# PrimaryLogger.net
KiCad netlist of a schematic drawn in EAGLE
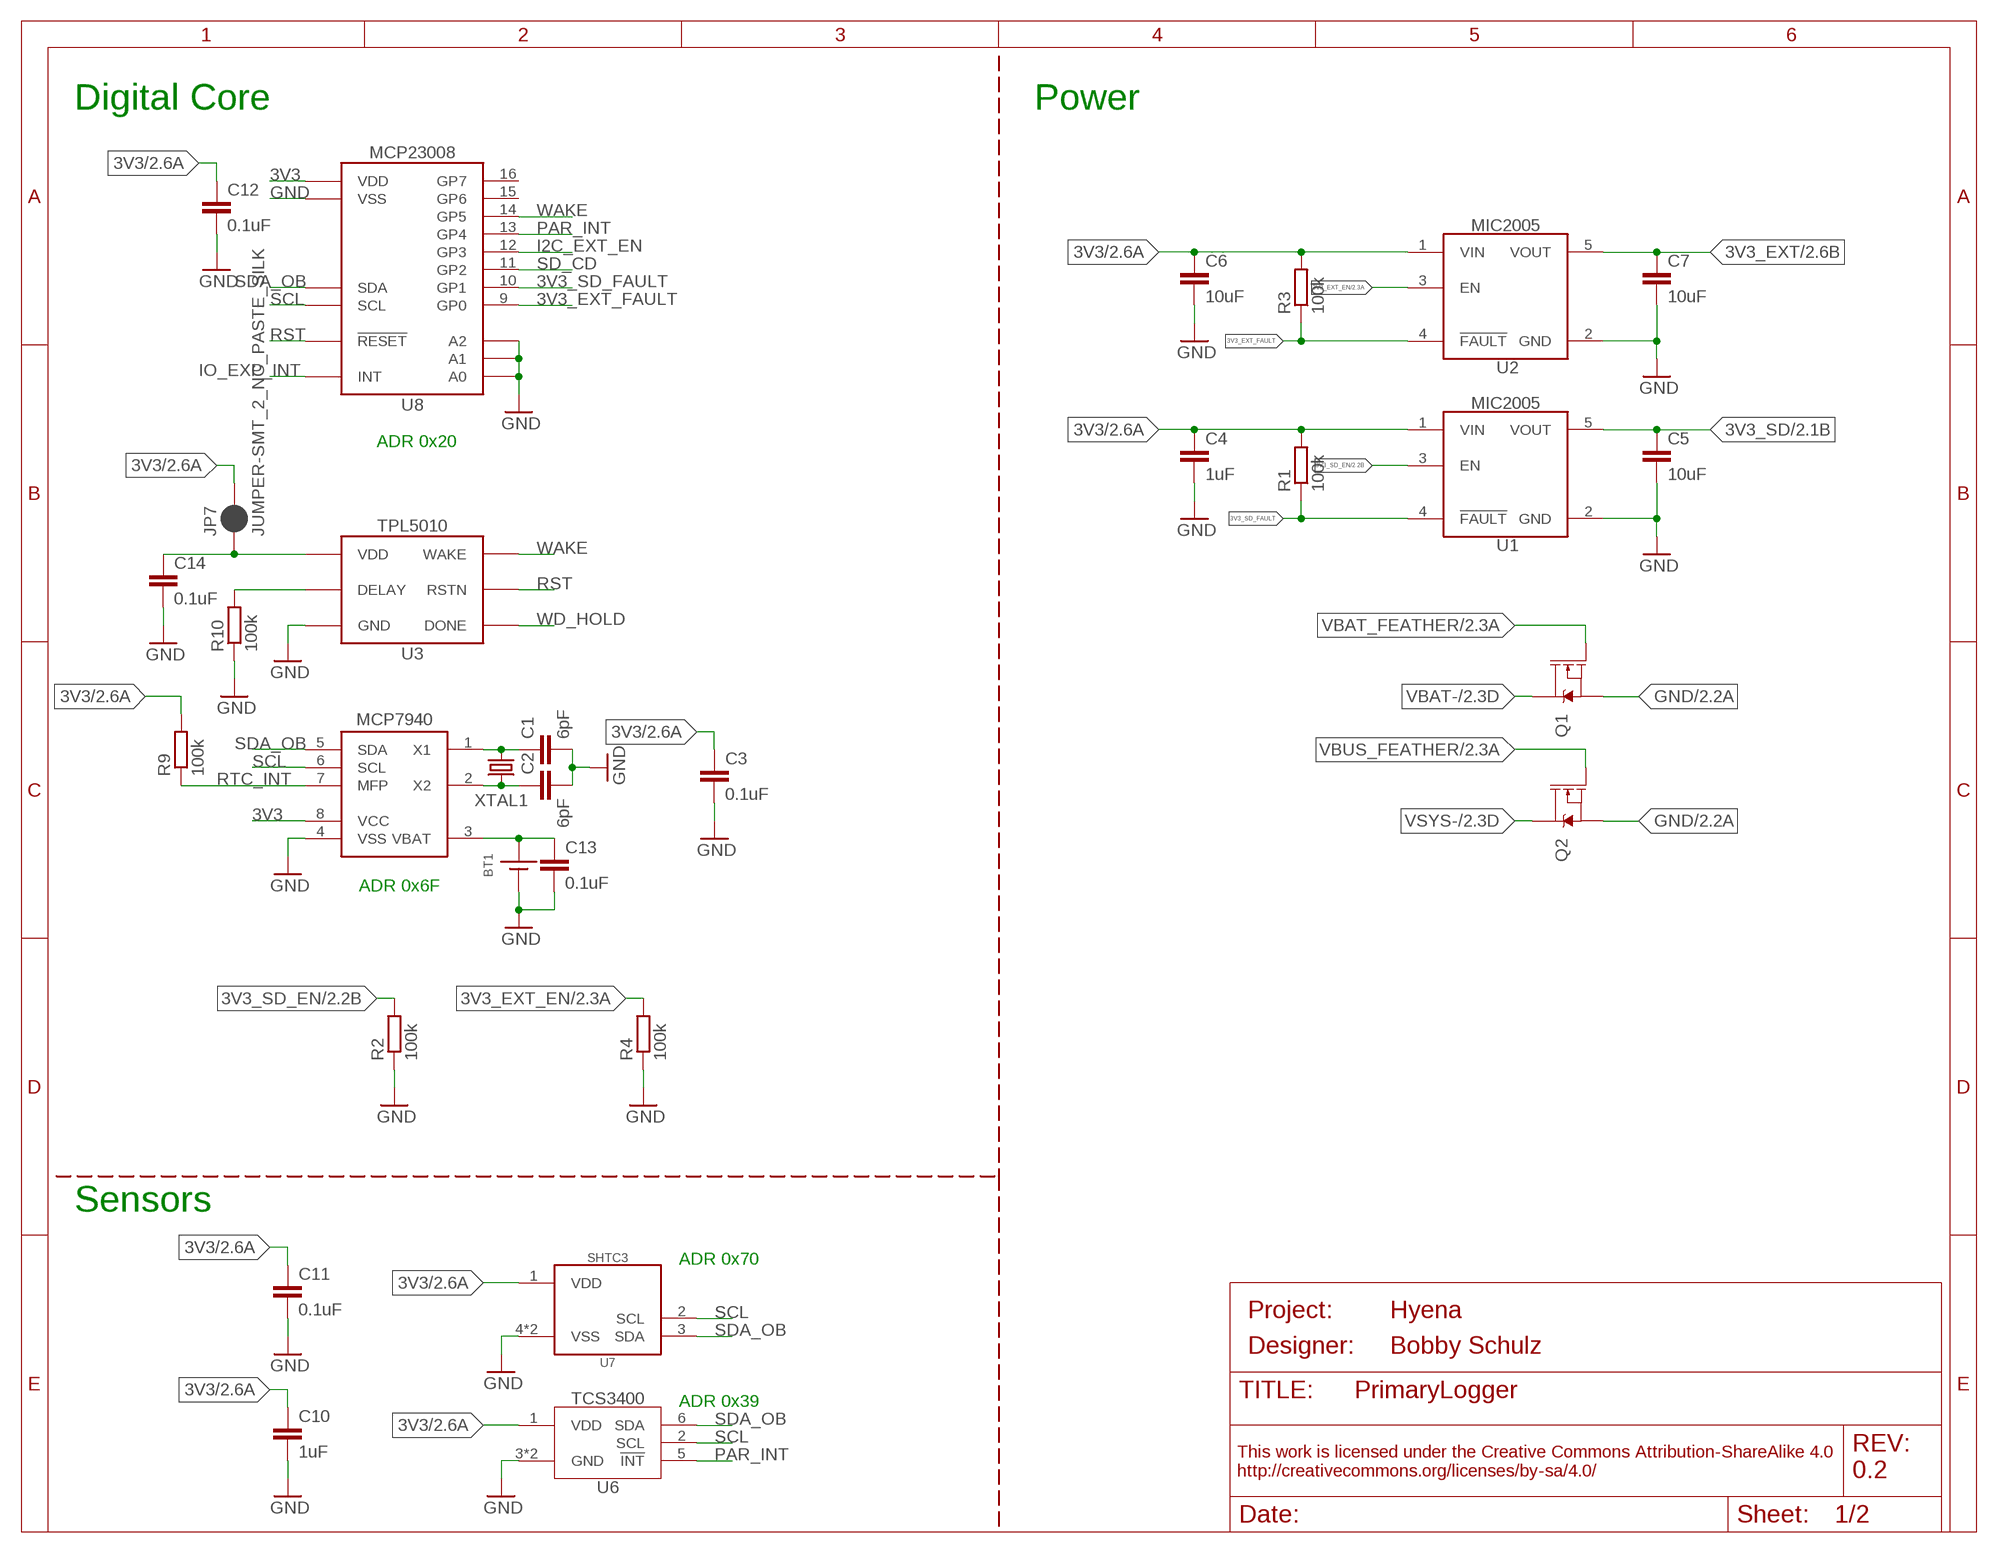
[diagram p0: schematic, sheet 1]
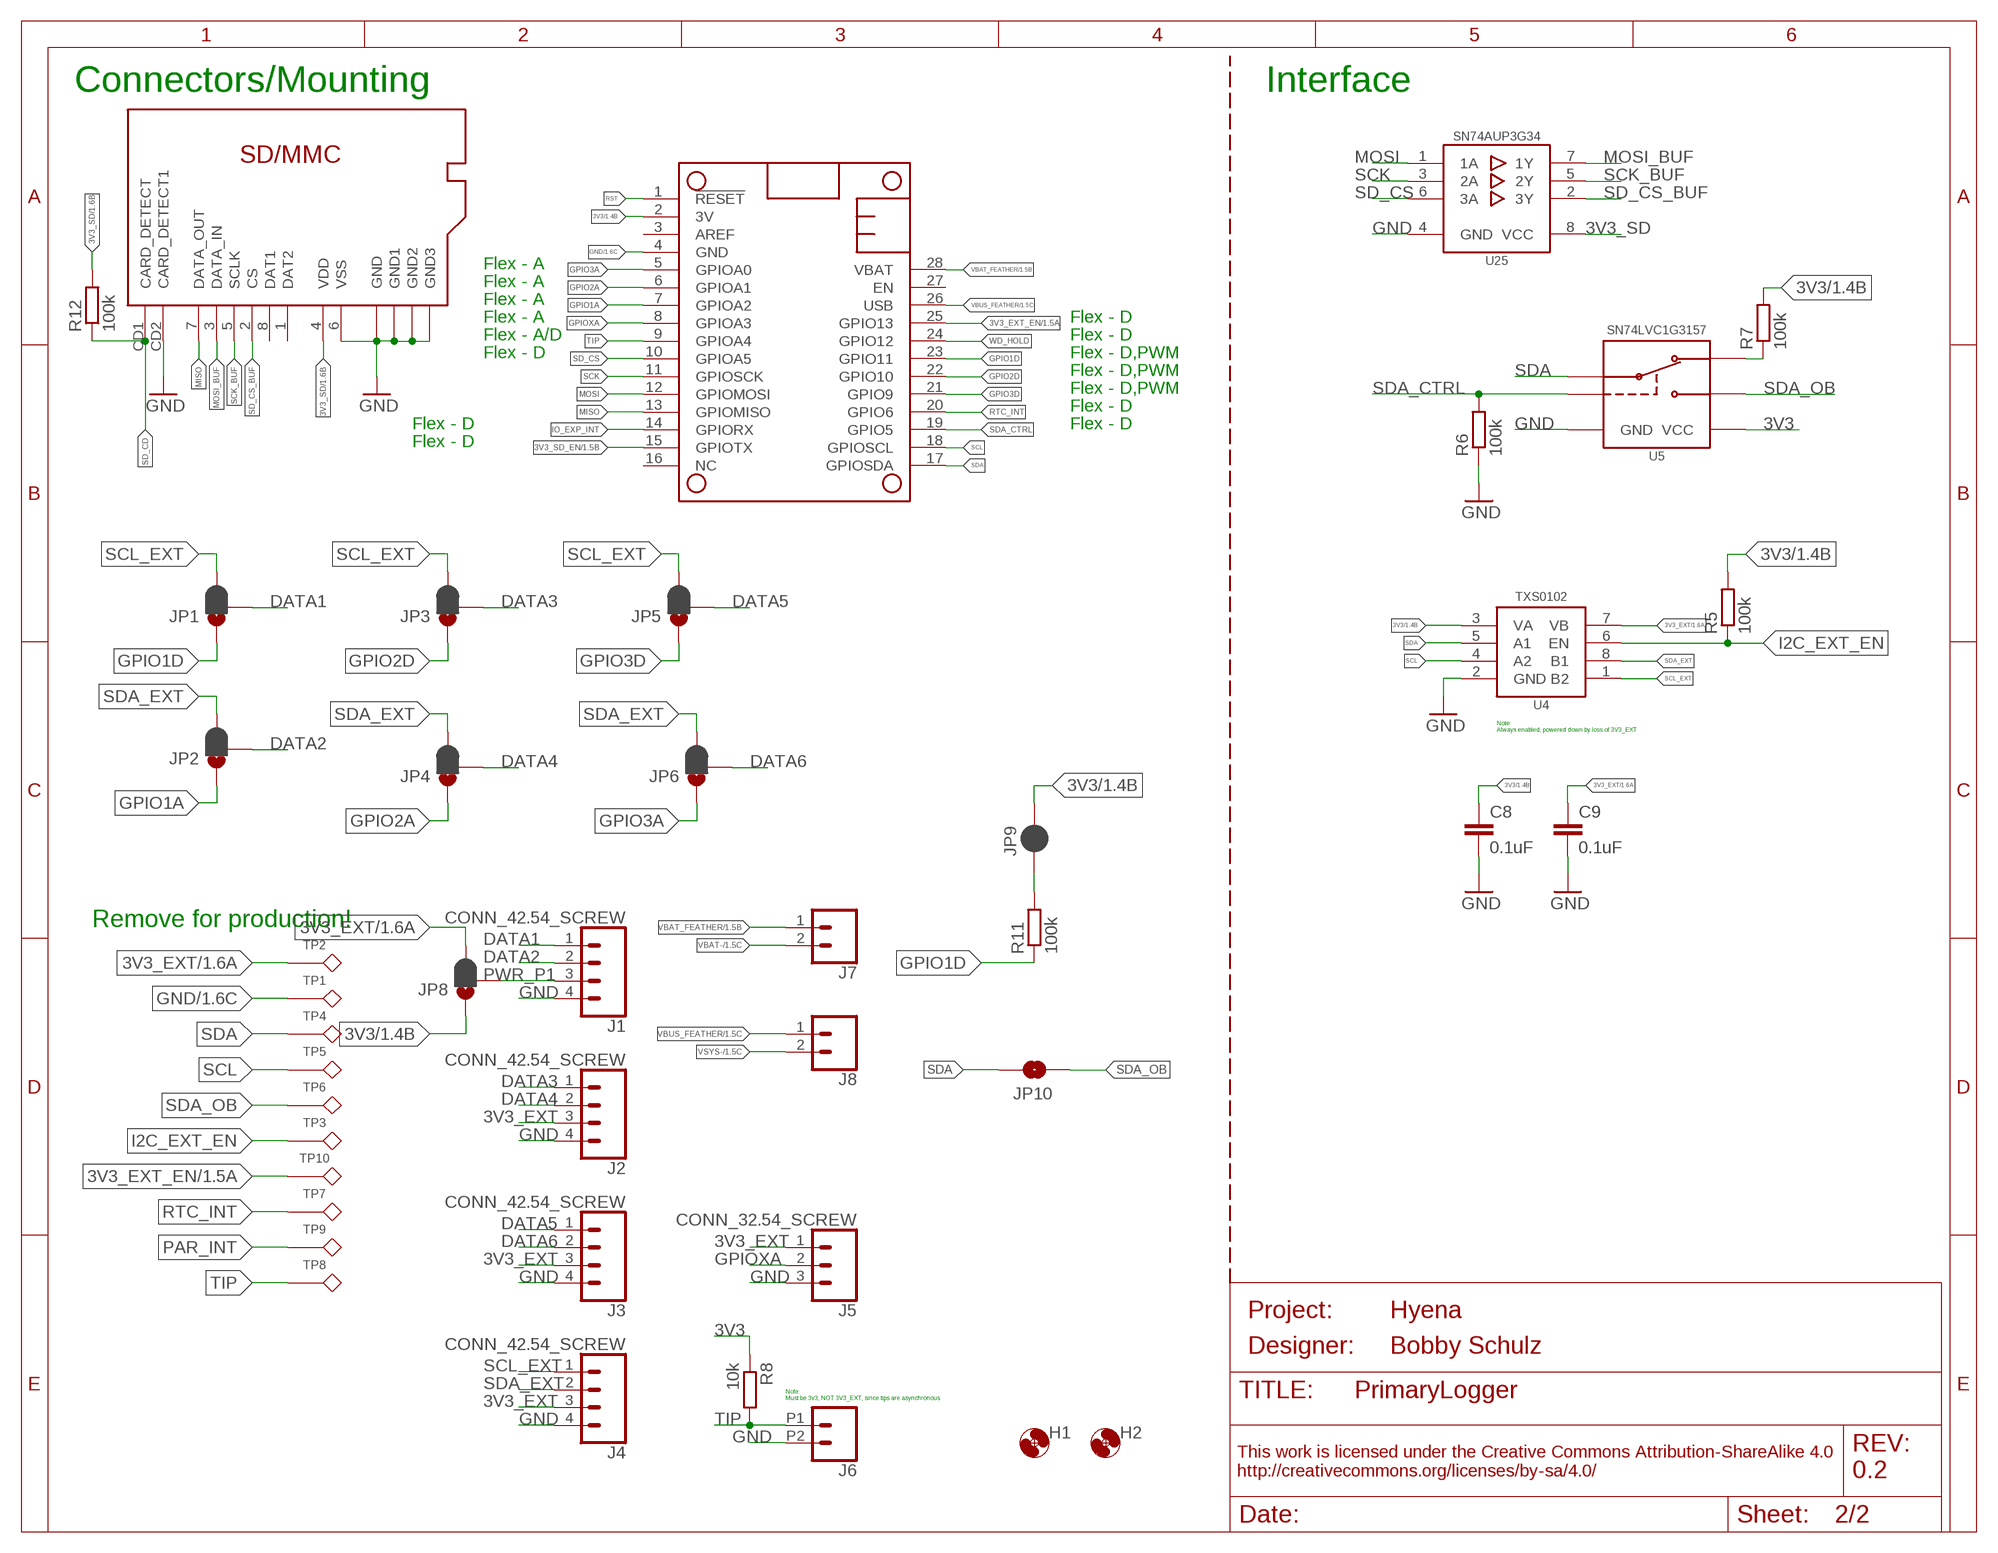
[diagram p1: schematic, sheet 2]

(export (version "E")
  (design (tool "Eeschema 10.0.6"))
  (components
    (comp (ref "BT1")
      (value "BATTERY_COIN12MM")
      (footprint "eagle-import:LINX_BAT-HLD-012-SMT")
      (fields (field (name "MF") "Linx") (field (name "MPN") "BAT-HLD-012-SMT"))
      (libsource (lib "eagle-import") (part "BATTERY_COIN12MM"))
    )
    (comp (ref "C1")
      (value "6pF")
      (footprint "eagle-import:C0402")
      (fields (field (name "MF") "Murata") (field (name "MPN") "GJM1555C1H6R0CB01D"))
      (libsource (lib "eagle-import") (part "C-EUC04026PF"))
    )
    (comp (ref "C2")
      (value "6pF")
      (footprint "eagle-import:C0402")
      (fields (field (name "MF") "Murata") (field (name "MPN") "GJM1555C1H6R0CB01D"))
      (libsource (lib "eagle-import") (part "C-EUC04026PF"))
    )
    (comp (ref "C3")
      (value "0.1uF")
      (footprint "eagle-import:C0603")
      (fields (field (name "MF") "Murata") (field (name "MPN") "GCM188R71E104KA57D"))
      (libsource (lib "eagle-import") (part "C-EUC06030.1UF"))
    )
    (comp (ref "C4")
      (value "1uF")
      (footprint "eagle-import:C0603")
      (fields (field (name "MF") "Yaiyo Yuden") (field (name "MPN") "EMK107BJ105KA-T"))
      (libsource (lib "eagle-import") (part "C-EUC06031UF"))
    )
    (comp (ref "C5")
      (value "10uF")
      (footprint "eagle-import:C0805")
      (fields (field (name "MF") "Murata") (field (name "MPN") "GRM21BR61C106KE15K"))
      (libsource (lib "eagle-import") (part "C-EUC080510UF"))
    )
    (comp (ref "C6")
      (value "10uF")
      (footprint "eagle-import:C0805")
      (fields (field (name "MF") "Murata") (field (name "MPN") "GRM21BR61C106KE15K"))
      (libsource (lib "eagle-import") (part "C-EUC080510UF"))
    )
    (comp (ref "C7")
      (value "10uF")
      (footprint "eagle-import:C0805")
      (fields (field (name "MF") "Murata") (field (name "MPN") "GRM21BR61C106KE15K"))
      (libsource (lib "eagle-import") (part "C-EUC080510UF"))
    )
    (comp (ref "C10")
      (value "1uF")
      (footprint "eagle-import:C0603")
      (fields (field (name "MF") "Yaiyo Yuden") (field (name "MPN") "EMK107BJ105KA-T"))
      (libsource (lib "eagle-import") (part "C-EUC06031UF"))
    )
    (comp (ref "C11")
      (value "0.1uF")
      (footprint "eagle-import:C0603")
      (fields (field (name "MF") "Murata") (field (name "MPN") "GCM188R71E104KA57D"))
      (libsource (lib "eagle-import") (part "C-EUC06030.1UF"))
    )
    (comp (ref "C12")
      (value "0.1uF")
      (footprint "eagle-import:C0603")
      (fields (field (name "MF") "Murata") (field (name "MPN") "GCM188R71E104KA57D"))
      (libsource (lib "eagle-import") (part "C-EUC06030.1UF"))
    )
    (comp (ref "C13")
      (value "0.1uF")
      (footprint "eagle-import:C0603")
      (fields (field (name "MF") "Murata") (field (name "MPN") "GCM188R71E104KA57D"))
      (libsource (lib "eagle-import") (part "C-EUC06030.1UF"))
    )
    (comp (ref "C14")
      (value "0.1uF")
      (footprint "eagle-import:C0603")
      (fields (field (name "MF") "Murata") (field (name "MPN") "GCM188R71E104KA57D"))
      (libsource (lib "eagle-import") (part "C-EUC06030.1UF"))
    )
    (comp (ref "JP7")
      (value "JUMPER-SMT_2_NC_PASTE_SILK")
      (footprint "eagle-import:SMT-JUMPER_2_NC_PASTE_SILK")
      (libsource (lib "eagle-import") (part "JUMPER-SMT_2_NC_PASTE_SILK"))
    )
    (comp (ref "Q1")
      (value "DMG3404")
      (footprint "eagle-import:SOT23-3")
      (fields (field (name "MF") "Diodes Incorporated") (field (name "MPN") "DMG3404L-7"))
      (libsource (lib "eagle-import") (part "MOSFET-NCH-DMG3404L"))
    )
    (comp (ref "Q2")
      (value "DMG3404")
      (footprint "eagle-import:SOT23-3")
      (fields (field (name "MF") "Diodes Incorporated") (field (name "MPN") "DMG3404L-7"))
      (libsource (lib "eagle-import") (part "MOSFET-NCH-DMG3404L"))
    )
    (comp (ref "R1")
      (value "100k")
      (footprint "eagle-import:R0603")
      (fields (field (name "MF") "Yageo") (field (name "MPN") "RC0603FR-07100KL"))
      (libsource (lib "eagle-import") (part "R-EU_R0603100K"))
    )
    (comp (ref "R2")
      (value "100k")
      (footprint "eagle-import:R0603")
      (fields (field (name "MF") "Yageo") (field (name "MPN") "RC0603FR-07100KL"))
      (libsource (lib "eagle-import") (part "R-EU_R0603100K"))
    )
    (comp (ref "R3")
      (value "100k")
      (footprint "eagle-import:R0603")
      (fields (field (name "MF") "Yageo") (field (name "MPN") "RC0603FR-07100KL"))
      (libsource (lib "eagle-import") (part "R-EU_R0603100K"))
    )
    (comp (ref "R4")
      (value "100k")
      (footprint "eagle-import:R0603")
      (fields (field (name "MF") "Yageo") (field (name "MPN") "RC0603FR-07100KL"))
      (libsource (lib "eagle-import") (part "R-EU_R0603100K"))
    )
    (comp (ref "R9")
      (value "100k")
      (footprint "eagle-import:R0603")
      (fields (field (name "MF") "Yageo") (field (name "MPN") "RC0603FR-07100KL"))
      (libsource (lib "eagle-import") (part "R-EU_R0603100K"))
    )
    (comp (ref "R10")
      (value "100k")
      (footprint "eagle-import:R0603")
      (fields (field (name "MF") "Yageo") (field (name "MPN") "RC0603FR-07100KL"))
      (libsource (lib "eagle-import") (part "R-EU_R0603100K"))
    )
    (comp (ref "U1")
      (value "MIC2005")
      (footprint "eagle-import:SOT23-5")
      (fields
        (field (name "DISP") "MIC2005")
        (field (name "MF") "Microchip")
        (field (name "MPN") "MIC2005A-1YM5-TR")
      )
      (libsource (lib "eagle-import") (part "MIC2005"))
    )
    (comp (ref "U2")
      (value "MIC2005")
      (footprint "eagle-import:SOT23-5")
      (fields
        (field (name "DISP") "MIC2005")
        (field (name "MF") "Microchip")
        (field (name "MPN") "MIC2005A-1YM5-TR")
      )
      (libsource (lib "eagle-import") (part "MIC2005"))
    )
    (comp (ref "U3")
      (value "TPL5010DDC")
      (footprint "eagle-import:DDC_R-PDSO-G6")
      (fields (field (name "MF") "TI") (field (name "MPN") "TPL5010DDCT"))
      (libsource (lib "eagle-import") (part "TPL5010DDC"))
    )
    (comp (ref "U6")
      (value "TCS3400")
      (footprint "eagle-import:TCS3400")
      (fields (field (name "MF") "AMS") (field (name "MPN") "TCS34003FNM"))
      (libsource (lib "eagle-import") (part "TCS3400"))
    )
    (comp (ref "U7")
      (value "SHTC3DFN")
      (footprint "eagle-import:DFN_4_2X2")
      (fields (field (name "DISP") "SHTC3") (field (name "MF") "Sensirion") (field (name "MPN") "SHTC3"))
      (libsource (lib "eagle-import") (part "SHTCDFN3"))
    )
    (comp (ref "U8")
      (value "MCP23008QFN")
      (footprint "eagle-import:QFN20")
      (fields (field (name "MF") "Microchip") (field (name "MPN") "MCP23008T-E/ML"))
      (libsource (lib "eagle-import") (part "MCP23008QFN"))
    )
    (comp (ref "U9")
      (value "MCP7940SOIC")
      (footprint "eagle-import:SO08")
      (fields (field (name "MF") "Microchip") (field (name "MPN") "MCP7940N-I/SN"))
      (libsource (lib "eagle-import") (part "MCP7940SOIC"))
    )
    (comp (ref "XTAL1")
      (value "CRYSTAL3.2X1.5")
      (footprint "eagle-import:CRYSTAL_3.2X1.5_2-SMD")
      (fields
        (field (name "DIGIKEY") "535-11937-1-ND")
        (field (name "MF") "ABS07-120-32.768KHZ-T")
        (field (name "MPN") "Abracon")
      )
      (libsource (lib "eagle-import") (part "CRYSTAL3.2X1.5"))
    )
    (comp (ref "C8")
      (value "0.1uF")
      (footprint "eagle-import:C0603")
      (fields (field (name "MF") "Murata") (field (name "MPN") "GCM188R71E104KA57D"))
      (libsource (lib "eagle-import") (part "C-EUC06030.1UF"))
    )
    (comp (ref "C9")
      (value "0.1uF")
      (footprint "eagle-import:C0603")
      (fields (field (name "MF") "Murata") (field (name "MPN") "GCM188R71E104KA57D"))
      (libsource (lib "eagle-import") (part "C-EUC06030.1UF"))
    )
    (comp (ref "H1")
      (value "MOUNTING_HOLE4_NP")
      (footprint "eagle-import:4_40")
      (fields (field (name "MPN") "DNP"))
      (libsource (lib "eagle-import") (part "MOUNTING_HOLE4_NP"))
    )
    (comp (ref "H2")
      (value "MOUNTING_HOLE4_NP")
      (footprint "eagle-import:4_40")
      (fields (field (name "MPN") "DNP"))
      (libsource (lib "eagle-import") (part "MOUNTING_HOLE4_NP"))
    )
    (comp (ref "J1")
      (value "CONN_42.54_SCREW")
      (footprint "eagle-import:1X04_SCREW")
      (fields (field (name "MF") "On Shore") (field (name "MPN") "OSTVN04A150"))
      (libsource (lib "eagle-import") (part "CONN_42.54_SCREW"))
    )
    (comp (ref "J2")
      (value "CONN_42.54_SCREW")
      (footprint "eagle-import:1X04_SCREW")
      (fields (field (name "MF") "On Shore") (field (name "MPN") "OSTVN04A150"))
      (libsource (lib "eagle-import") (part "CONN_42.54_SCREW"))
    )
    (comp (ref "J3")
      (value "CONN_42.54_SCREW")
      (footprint "eagle-import:1X04_SCREW")
      (fields (field (name "MF") "On Shore") (field (name "MPN") "OSTVN04A150"))
      (libsource (lib "eagle-import") (part "CONN_42.54_SCREW"))
    )
    (comp (ref "J4")
      (value "CONN_42.54_SCREW")
      (footprint "eagle-import:1X04_SCREW")
      (fields (field (name "MF") "On Shore") (field (name "MPN") "OSTVN04A150"))
      (libsource (lib "eagle-import") (part "CONN_42.54_SCREW"))
    )
    (comp (ref "J5")
      (value "CONN_32.54_SCREW")
      (footprint "eagle-import:1X03_SCREW")
      (fields (field (name "MF") "On Shore") (field (name "MPN") "OSTVN03A150"))
      (libsource (lib "eagle-import") (part "CONN_32.54_SCREW"))
    )
    (comp (ref "J6")
      (value "CONN_022.54_SCREW_ROUND")
      (footprint "eagle-import:1X02_2.54_SCREWTERM_ROUND")
      (fields (field (name "MF") "OnShore") (field (name "MPN") "OSTVN02A150"))
      (libsource (lib "eagle-import") (part "CONN_022.54_SCREW_ROUND"))
    )
    (comp (ref "J7")
      (value "CONN_023.5MM_ROUND")
      (footprint "eagle-import:SCREWTERMINAL-3.5MM-2_ROUND")
      (fields (field (name "MF") "OnShore") (field (name "MPN") "OSTTE020161"))
      (libsource (lib "eagle-import") (part "CONN_023.5MM_ROUND"))
    )
    (comp (ref "J8")
      (value "CONN_023.5MM_ROUND")
      (footprint "eagle-import:SCREWTERMINAL-3.5MM-2_ROUND")
      (fields (field (name "MF") "OnShore") (field (name "MPN") "OSTTE020161"))
      (libsource (lib "eagle-import") (part "CONN_023.5MM_ROUND"))
    )
    (comp (ref "JP1")
      (value "JUMPER-SMT_3_1-NC_PASTE_SILK")
      (footprint "eagle-import:SMT-JUMPER_3_1-NC_PASTE_SILK")
      (libsource (lib "eagle-import") (part "JUMPER-SMT_3_1-NC_PASTE_SILK"))
    )
    (comp (ref "JP2")
      (value "JUMPER-SMT_3_1-NC_PASTE_SILK")
      (footprint "eagle-import:SMT-JUMPER_3_1-NC_PASTE_SILK")
      (libsource (lib "eagle-import") (part "JUMPER-SMT_3_1-NC_PASTE_SILK"))
    )
    (comp (ref "JP3")
      (value "JUMPER-SMT_3_1-NC_PASTE_SILK")
      (footprint "eagle-import:SMT-JUMPER_3_1-NC_PASTE_SILK")
      (libsource (lib "eagle-import") (part "JUMPER-SMT_3_1-NC_PASTE_SILK"))
    )
    (comp (ref "JP4")
      (value "JUMPER-SMT_3_1-NC_PASTE_SILK")
      (footprint "eagle-import:SMT-JUMPER_3_1-NC_PASTE_SILK")
      (libsource (lib "eagle-import") (part "JUMPER-SMT_3_1-NC_PASTE_SILK"))
    )
    (comp (ref "JP5")
      (value "JUMPER-SMT_3_1-NC_PASTE_SILK")
      (footprint "eagle-import:SMT-JUMPER_3_1-NC_PASTE_SILK")
      (libsource (lib "eagle-import") (part "JUMPER-SMT_3_1-NC_PASTE_SILK"))
    )
    (comp (ref "JP6")
      (value "JUMPER-SMT_3_1-NC_PASTE_SILK")
      (footprint "eagle-import:SMT-JUMPER_3_1-NC_PASTE_SILK")
      (libsource (lib "eagle-import") (part "JUMPER-SMT_3_1-NC_PASTE_SILK"))
    )
    (comp (ref "JP8")
      (value "JUMPER-SMT_3_1-NC_PASTE_SILK")
      (footprint "eagle-import:SMT-JUMPER_3_1-NC_PASTE_SILK")
      (libsource (lib "eagle-import") (part "JUMPER-SMT_3_1-NC_PASTE_SILK"))
    )
    (comp (ref "JP9")
      (value "JUMPER-SMT_2_NC_PASTE_SILK")
      (footprint "eagle-import:SMT-JUMPER_2_NC_PASTE_SILK")
      (libsource (lib "eagle-import") (part "JUMPER-SMT_2_NC_PASTE_SILK"))
    )
    (comp (ref "JP10")
      (value "JUMPER-SMT_2_NO_SILK")
      (footprint "eagle-import:SMT-JUMPER_2_NO_SILK")
      (libsource (lib "eagle-import") (part "JUMPER-SMT_2_NO_SILK"))
    )
    (comp (ref "MS1")
      (value "FEATHERWING_NODIM")
      (footprint "eagle-import:FEATHERWING_DIM")
      (libsource (lib "eagle-import") (part "FEATHERWING_NODIM"))
    )
    (comp (ref "R5")
      (value "100k")
      (footprint "eagle-import:R0603")
      (fields (field (name "MF") "Yageo") (field (name "MPN") "RC0603FR-07100KL"))
      (libsource (lib "eagle-import") (part "R-EU_R0603100K"))
    )
    (comp (ref "R6")
      (value "100k")
      (footprint "eagle-import:R0603")
      (fields (field (name "MF") "Yageo") (field (name "MPN") "RC0603FR-07100KL"))
      (libsource (lib "eagle-import") (part "R-EU_R0603100K"))
    )
    (comp (ref "R7")
      (value "100k")
      (footprint "eagle-import:R0603")
      (fields (field (name "MF") "Yageo") (field (name "MPN") "RC0603FR-07100KL"))
      (libsource (lib "eagle-import") (part "R-EU_R0603100K"))
    )
    (comp (ref "R8")
      (value "10k")
      (footprint "eagle-import:R0603")
      (fields (field (name "MF") "Yageo") (field (name "MPN") "RC0603FR-0710KL"))
      (libsource (lib "eagle-import") (part "R-EU_R060310K"))
    )
    (comp (ref "R11")
      (value "100k")
      (footprint "eagle-import:R0603")
      (fields (field (name "MF") "Yageo") (field (name "MPN") "RC0603FR-07100KL"))
      (libsource (lib "eagle-import") (part "R-EU_R0603100K"))
    )
    (comp (ref "R12")
      (value "100k")
      (footprint "eagle-import:R0603")
      (fields (field (name "MF") "Yageo") (field (name "MPN") "RC0603FR-07100KL"))
      (libsource (lib "eagle-import") (part "R-EU_R0603100K"))
    )
    (comp (ref "SD1")
      (value "MICRO_SD")
      (footprint "eagle-import:CUSTOM-PARTS_SD_MICRO")
      (fields (field (name "MF") "Amphenol") (field (name "MPN") "114-00841-68"))
      (libsource (lib "eagle-import") (part "MICRO_SD"))
    )
    (comp (ref "TP1")
      (value "TESTPOINTRCU")
      (footprint "eagle-import:TESTPOINT_0603")
      (fields (field (name "MF") "TE Connectivity") (field (name "MPN") "RCU-0C"))
      (libsource (lib "eagle-import") (part "TESTPOINTRCU"))
    )
    (comp (ref "TP2")
      (value "TESTPOINTRCU")
      (footprint "eagle-import:TESTPOINT_0603")
      (fields (field (name "MF") "TE Connectivity") (field (name "MPN") "RCU-0C"))
      (libsource (lib "eagle-import") (part "TESTPOINTRCU"))
    )
    (comp (ref "TP3")
      (value "TESTPOINTRCU")
      (footprint "eagle-import:TESTPOINT_0603")
      (fields (field (name "MF") "TE Connectivity") (field (name "MPN") "RCU-0C"))
      (libsource (lib "eagle-import") (part "TESTPOINTRCU"))
    )
    (comp (ref "TP4")
      (value "TESTPOINTRCU")
      (footprint "eagle-import:TESTPOINT_0603")
      (fields (field (name "MF") "TE Connectivity") (field (name "MPN") "RCU-0C"))
      (libsource (lib "eagle-import") (part "TESTPOINTRCU"))
    )
    (comp (ref "TP5")
      (value "TESTPOINTRCU")
      (footprint "eagle-import:TESTPOINT_0603")
      (fields (field (name "MF") "TE Connectivity") (field (name "MPN") "RCU-0C"))
      (libsource (lib "eagle-import") (part "TESTPOINTRCU"))
    )
    (comp (ref "TP6")
      (value "TESTPOINTRCU")
      (footprint "eagle-import:TESTPOINT_0603")
      (fields (field (name "MF") "TE Connectivity") (field (name "MPN") "RCU-0C"))
      (libsource (lib "eagle-import") (part "TESTPOINTRCU"))
    )
    (comp (ref "TP7")
      (value "TESTPOINTRCU")
      (footprint "eagle-import:TESTPOINT_0603")
      (fields (field (name "MF") "TE Connectivity") (field (name "MPN") "RCU-0C"))
      (libsource (lib "eagle-import") (part "TESTPOINTRCU"))
    )
    (comp (ref "TP8")
      (value "TESTPOINTRCU")
      (footprint "eagle-import:TESTPOINT_0603")
      (fields (field (name "MF") "TE Connectivity") (field (name "MPN") "RCU-0C"))
      (libsource (lib "eagle-import") (part "TESTPOINTRCU"))
    )
    (comp (ref "TP9")
      (value "TESTPOINTRCU")
      (footprint "eagle-import:TESTPOINT_0603")
      (fields (field (name "MF") "TE Connectivity") (field (name "MPN") "RCU-0C"))
      (libsource (lib "eagle-import") (part "TESTPOINTRCU"))
    )
    (comp (ref "TP10")
      (value "TESTPOINTRCU")
      (footprint "eagle-import:TESTPOINT_0603")
      (fields (field (name "MF") "TE Connectivity") (field (name "MPN") "RCU-0C"))
      (libsource (lib "eagle-import") (part "TESTPOINTRCU"))
    )
    (comp (ref "U4")
      (value "TXS0102DCU")
      (footprint "eagle-import:DCU_(R-PDSO-G8)")
      (fields (field (name "MF") "TI") (field (name "MPN") "TXS0102DCUR"))
      (libsource (lib "eagle-import") (part "TXS0102DCU"))
    )
    (comp (ref "U5")
      (value "SN74LVC1G3157SC70")
      (footprint "eagle-import:DCK_R-PDSO-G6")
      (fields
        (field (name "DISP") "SN74LVC1G3157")
        (field (name "MF") "TI")
        (field (name "MPN") "SN74LVC1G3157DCKR")
      )
      (libsource (lib "eagle-import") (part "SN74LVC1G3157SC70"))
    )
    (comp (ref "U25")
      (value "SN74AUP3G34DCU")
      (footprint "eagle-import:DCU_(R-PDSO-G8)")
      (fields (field (name "MF") "TI") (field (name "MPN") "SN74AUP3G34DCUR"))
      (libsource (lib "eagle-import") (part "SN74AUP3G34DCU"))
    )
  )
  (nets
    (net (code "1") (name "3V3") (class "Default")
      (node (ref "C10") (pin "1") (pinfunction "1_1") (pintype "passive"))
      (node (ref "C11") (pin "1") (pinfunction "1_1") (pintype "passive"))
      (node (ref "C12") (pin "1") (pinfunction "1_1") (pintype "passive"))
      (node (ref "C3") (pin "1") (pinfunction "1_1") (pintype "passive"))
      (node (ref "C4") (pin "1") (pinfunction "1_1") (pintype "passive"))
      (node (ref "C6") (pin "1") (pinfunction "1_1") (pintype "passive"))
      (node (ref "C8") (pin "1") (pinfunction "1_1") (pintype "passive"))
      (node (ref "JP7") (pin "2") (pinfunction "2_2") (pintype "passive"))
      (node (ref "JP8") (pin "1") (pinfunction "1_1") (pintype "passive"))
      (node (ref "JP9") (pin "2") (pinfunction "2_2") (pintype "passive"))
      (node (ref "MS1") (pin "2") (pinfunction "3V_2") (pintype "power_in"))
      (node (ref "R1") (pin "2") (pinfunction "2_2") (pintype "passive"))
      (node (ref "R3") (pin "2") (pinfunction "2_2") (pintype "passive"))
      (node (ref "R5") (pin "2") (pinfunction "2_2") (pintype "passive"))
      (node (ref "R7") (pin "2") (pinfunction "2_2") (pintype "passive"))
      (node (ref "R8") (pin "1") (pinfunction "1_1") (pintype "passive"))
      (node (ref "R9") (pin "2") (pinfunction "2_2") (pintype "passive"))
      (node (ref "U1") (pin "1") (pinfunction "VIN_1") (pintype "power_in"))
      (node (ref "U2") (pin "1") (pinfunction "VIN_1") (pintype "power_in"))
      (node (ref "U4") (pin "3") (pinfunction "VA_3") (pintype "power_in"))
      (node (ref "U5") (pin "5") (pinfunction "VCC_5") (pintype "power_in"))
      (node (ref "U6") (pin "1") (pinfunction "VDD_1") (pintype "power_in"))
      (node (ref "U7") (pin "1") (pinfunction "VDD_1") (pintype "power_in"))
      (node (ref "U8") (pin "18") (pinfunction "VDD_18") (pintype "power_in"))
      (node (ref "U9") (pin "8") (pinfunction "VCC_8") (pintype "bidirectional"))
    )
    (net (code "2") (name "3V3_EXT") (class "Default")
      (node (ref "C7") (pin "1") (pinfunction "1_1") (pintype "passive"))
      (node (ref "C9") (pin "1") (pinfunction "1_1") (pintype "passive"))
      (node (ref "J2") (pin "3") (pinfunction "3_3") (pintype "passive"))
      (node (ref "J3") (pin "3") (pinfunction "3_3") (pintype "passive"))
      (node (ref "J4") (pin "3") (pinfunction "3_3") (pintype "passive"))
      (node (ref "J5") (pin "1") (pinfunction "1_1") (pintype "passive"))
      (node (ref "JP8") (pin "3") (pinfunction "3_3") (pintype "passive"))
      (node (ref "TP2") (pin "1") (pinfunction "P$1_1") (pintype "bidirectional"))
      (node (ref "U2") (pin "5") (pinfunction "VOUT_5") (pintype "power_in"))
      (node (ref "U4") (pin "7") (pinfunction "VB_7") (pintype "power_in"))
    )
    (net (code "3") (name "3V3_EXT_EN") (class "Default")
      (node (ref "MS1") (pin "25") (pinfunction "GPIO13_25") (pintype "bidirectional"))
      (node (ref "R4") (pin "2") (pinfunction "2_2") (pintype "passive"))
      (node (ref "TP10") (pin "1") (pinfunction "P$1_1") (pintype "bidirectional"))
      (node (ref "U2") (pin "3") (pinfunction "EN_3") (pintype "input"))
    )
    (net (code "4") (name "3V3_EXT_FAULT") (class "Default")
      (node (ref "R3") (pin "1") (pinfunction "1_1") (pintype "passive"))
      (node (ref "U2") (pin "4") (pinfunction "~{FAULT}_4") (pintype "output"))
      (node (ref "U8") (pin "9") (pinfunction "GP0_9") (pintype "bidirectional"))
    )
    (net (code "5") (name "3V3_SD") (class "Default")
      (node (ref "C5") (pin "1") (pinfunction "1_1") (pintype "passive"))
      (node (ref "R12") (pin "2") (pinfunction "2_2") (pintype "passive"))
      (node (ref "SD1") (pin "4") (pinfunction "VDD_4") (pintype "bidirectional"))
      (node (ref "U1") (pin "5") (pinfunction "VOUT_5") (pintype "power_in"))
      (node (ref "U25") (pin "8") (pinfunction "VCC_8") (pintype "power_in"))
    )
    (net (code "6") (name "3V3_SD_EN") (class "Default")
      (node (ref "MS1") (pin "15") (pinfunction "GPIOTX_15") (pintype "bidirectional"))
      (node (ref "R2") (pin "2") (pinfunction "2_2") (pintype "passive"))
      (node (ref "U1") (pin "3") (pinfunction "EN_3") (pintype "input"))
    )
    (net (code "7") (name "3V3_SD_FAULT") (class "Default")
      (node (ref "R1") (pin "1") (pinfunction "1_1") (pintype "passive"))
      (node (ref "U1") (pin "4") (pinfunction "~{FAULT}_4") (pintype "output"))
      (node (ref "U8") (pin "10") (pinfunction "GP1_10") (pintype "bidirectional"))
    )
    (net (code "8") (name "DATA1") (class "Default")
      (node (ref "J1") (pin "1") (pinfunction "1_1") (pintype "passive"))
      (node (ref "JP1") (pin "2") (pinfunction "2_2") (pintype "passive"))
    )
    (net (code "9") (name "DATA2") (class "Default")
      (node (ref "J1") (pin "2") (pinfunction "2_2") (pintype "passive"))
      (node (ref "JP2") (pin "2") (pinfunction "2_2") (pintype "passive"))
    )
    (net (code "10") (name "DATA3") (class "Default")
      (node (ref "J2") (pin "1") (pinfunction "1_1") (pintype "passive"))
      (node (ref "JP3") (pin "2") (pinfunction "2_2") (pintype "passive"))
    )
    (net (code "11") (name "DATA4") (class "Default")
      (node (ref "J2") (pin "2") (pinfunction "2_2") (pintype "passive"))
      (node (ref "JP4") (pin "2") (pinfunction "2_2") (pintype "passive"))
    )
    (net (code "12") (name "DATA5") (class "Default")
      (node (ref "J3") (pin "1") (pinfunction "1_1") (pintype "passive"))
      (node (ref "JP5") (pin "2") (pinfunction "2_2") (pintype "passive"))
    )
    (net (code "13") (name "DATA6") (class "Default")
      (node (ref "J3") (pin "2") (pinfunction "2_2") (pintype "passive"))
      (node (ref "JP6") (pin "2") (pinfunction "2_2") (pintype "passive"))
    )
    (net (code "14") (name "GND") (class "Default")
      (node (ref "BT1") (pin "GND") (pinfunction "-_GND") (pintype "bidirectional"))
      (node (ref "C1") (pin "2") (pinfunction "2_2") (pintype "passive"))
      (node (ref "C10") (pin "2") (pinfunction "2_2") (pintype "passive"))
      (node (ref "C11") (pin "2") (pinfunction "2_2") (pintype "passive"))
      (node (ref "C12") (pin "2") (pinfunction "2_2") (pintype "passive"))
      (node (ref "C13") (pin "2") (pinfunction "2_2") (pintype "passive"))
      (node (ref "C14") (pin "2") (pinfunction "2_2") (pintype "passive"))
      (node (ref "C2") (pin "2") (pinfunction "2_2") (pintype "passive"))
      (node (ref "C3") (pin "2") (pinfunction "2_2") (pintype "passive"))
      (node (ref "C4") (pin "2") (pinfunction "2_2") (pintype "passive"))
      (node (ref "C5") (pin "2") (pinfunction "2_2") (pintype "passive"))
      (node (ref "C6") (pin "2") (pinfunction "2_2") (pintype "passive"))
      (node (ref "C7") (pin "2") (pinfunction "2_2") (pintype "passive"))
      (node (ref "C8") (pin "2") (pinfunction "2_2") (pintype "passive"))
      (node (ref "C9") (pin "2") (pinfunction "2_2") (pintype "passive"))
      (node (ref "J1") (pin "4") (pinfunction "4_4") (pintype "passive"))
      (node (ref "J2") (pin "4") (pinfunction "4_4") (pintype "passive"))
      (node (ref "J3") (pin "4") (pinfunction "4_4") (pintype "passive"))
      (node (ref "J4") (pin "4") (pinfunction "4_4") (pintype "passive"))
      (node (ref "J5") (pin "3") (pinfunction "3_3") (pintype "passive"))
      (node (ref "J6") (pin "P2") (pinfunction "2_P2") (pintype "passive"))
      (node (ref "MS1") (pin "4") (pinfunction "GND_4") (pintype "power_in"))
      (node (ref "Q1") (pin "2") (pinfunction "S_2") (pintype "bidirectional"))
      (node (ref "Q2") (pin "2") (pinfunction "S_2") (pintype "bidirectional"))
      (node (ref "R10") (pin "1") (pinfunction "1_1") (pintype "passive"))
      (node (ref "R2") (pin "1") (pinfunction "1_1") (pintype "passive"))
      (node (ref "R4") (pin "1") (pinfunction "1_1") (pintype "passive"))
      (node (ref "R6") (pin "1") (pinfunction "1_1") (pintype "passive"))
      (node (ref "SD1") (pin "6") (pinfunction "VSS_6") (pintype "bidirectional"))
      (node (ref "SD1") (pin "CD2") (pinfunction "CARD_DETECT1_CD2") (pintype "bidirectional"))
      (node (ref "SD1") (pin "GND@1") (pinfunction "GND_GND@1") (pintype "bidirectional"))
      (node (ref "SD1") (pin "GND@2") (pinfunction "GND1_GND@2") (pintype "bidirectional"))
      (node (ref "SD1") (pin "GND@3") (pinfunction "GND2_GND@3") (pintype "bidirectional"))
      (node (ref "SD1") (pin "GND@5") (pinfunction "GND3_GND@5") (pintype "bidirectional"))
      (node (ref "TP1") (pin "1") (pinfunction "P$1_1") (pintype "bidirectional"))
      (node (ref "U1") (pin "2") (pinfunction "GND_2") (pintype "power_in"))
      (node (ref "U2") (pin "2") (pinfunction "GND_2") (pintype "power_in"))
      (node (ref "U25") (pin "4") (pinfunction "GND_4") (pintype "power_in"))
      (node (ref "U3") (pin "2") (pinfunction "GND_2") (pintype "power_in"))
      (node (ref "U4") (pin "2") (pinfunction "GND_2") (pintype "power_in"))
      (node (ref "U5") (pin "2") (pinfunction "GND_2") (pintype "power_in"))
      (node (ref "U6") (pin "3") (pinfunction "GND_3") (pintype "power_in"))
      (node (ref "U6") (pin "4") (pinfunction "GND_4") (pintype "power_in"))
      (node (ref "U7") (pin "4") (pinfunction "VSS_4") (pintype "power_in"))
      (node (ref "U7") (pin "EP") (pinfunction "VSS_EP") (pintype "power_in"))
      (node (ref "U8") (pin "1") (pinfunction "A2_1") (pintype "input"))
      (node (ref "U8") (pin "17") (pinfunction "VSS_17") (pintype "power_in"))
      (node (ref "U8") (pin "2") (pinfunction "A1_2") (pintype "input"))
      (node (ref "U8") (pin "3") (pinfunction "A0_3") (pintype "input"))
      (node (ref "U8") (pin "EP") (pinfunction "VSS_EP") (pintype "power_in"))
      (node (ref "U9") (pin "4") (pinfunction "VSS_4") (pintype "bidirectional"))
    )
    (net (code "15") (name "GPIO1A") (class "Default")
      (node (ref "JP2") (pin "1") (pinfunction "1_1") (pintype "passive"))
      (node (ref "MS1") (pin "7") (pinfunction "GPIOA2_7") (pintype "bidirectional"))
    )
    (net (code "16") (name "GPIO1D") (class "Default")
      (node (ref "JP1") (pin "1") (pinfunction "1_1") (pintype "passive"))
      (node (ref "MS1") (pin "23") (pinfunction "GPIO11_23") (pintype "bidirectional"))
      (node (ref "R11") (pin "1") (pinfunction "1_1") (pintype "passive"))
    )
    (net (code "17") (name "GPIO2A") (class "Default")
      (node (ref "JP4") (pin "1") (pinfunction "1_1") (pintype "passive"))
      (node (ref "MS1") (pin "6") (pinfunction "GPIOA1_6") (pintype "bidirectional"))
    )
    (net (code "18") (name "GPIO2D") (class "Default")
      (node (ref "JP3") (pin "1") (pinfunction "1_1") (pintype "passive"))
      (node (ref "MS1") (pin "22") (pinfunction "GPIO10_22") (pintype "bidirectional"))
    )
    (net (code "19") (name "GPIO3A") (class "Default")
      (node (ref "JP6") (pin "1") (pinfunction "1_1") (pintype "passive"))
      (node (ref "MS1") (pin "5") (pinfunction "GPIOA0_5") (pintype "bidirectional"))
    )
    (net (code "20") (name "GPIO3D") (class "Default")
      (node (ref "JP5") (pin "1") (pinfunction "1_1") (pintype "passive"))
      (node (ref "MS1") (pin "21") (pinfunction "GPIO9_21") (pintype "bidirectional"))
    )
    (net (code "21") (name "GPIOXA") (class "Default")
      (node (ref "J5") (pin "2") (pinfunction "2_2") (pintype "passive"))
      (node (ref "MS1") (pin "8") (pinfunction "GPIOA3_8") (pintype "bidirectional"))
    )
    (net (code "22") (name "I2C_EXT_EN") (class "Default")
      (node (ref "R5") (pin "1") (pinfunction "1_1") (pintype "passive"))
      (node (ref "TP3") (pin "1") (pinfunction "P$1_1") (pintype "bidirectional"))
      (node (ref "U4") (pin "6") (pinfunction "EN_6") (pintype "input"))
      (node (ref "U8") (pin "12") (pinfunction "GP3_12") (pintype "bidirectional"))
    )
    (net (code "23") (name "IO_EXP_INT") (class "Default")
      (node (ref "MS1") (pin "14") (pinfunction "GPIORX_14") (pintype "bidirectional"))
      (node (ref "U8") (pin "7") (pinfunction "INT_7") (pintype "output"))
    )
    (net (code "24") (name "MISO") (class "Default")
      (node (ref "MS1") (pin "13") (pinfunction "GPIOMISO_13") (pintype "bidirectional"))
      (node (ref "SD1") (pin "7") (pinfunction "DATA_OUT_7") (pintype "bidirectional"))
    )
    (net (code "25") (name "MOSI") (class "Default")
      (node (ref "MS1") (pin "12") (pinfunction "GPIOMOSI_12") (pintype "bidirectional"))
      (node (ref "U25") (pin "1") (pinfunction "1A_1") (pintype "input"))
    )
    (net (code "26") (name "MOSI_BUF") (class "Default")
      (node (ref "SD1") (pin "3") (pinfunction "DATA_IN_3") (pintype "bidirectional"))
      (node (ref "U25") (pin "7") (pinfunction "1Y_7") (pintype "output"))
    )
    (net (code "27") (name "Net-(JP9-Pad1)") (class "Default")
      (node (ref "JP9") (pin "1") (pinfunction "1_1") (pintype "passive"))
      (node (ref "R11") (pin "2") (pinfunction "2_2") (pintype "passive"))
    )
    (net (code "28") (name "Net-(U3-DELAY)") (class "Default")
      (node (ref "R10") (pin "2") (pinfunction "2_2") (pintype "passive"))
      (node (ref "U3") (pin "3") (pinfunction "DELAY_3") (pintype "input"))
    )
    (net (code "29") (name "Net-(U3-VDD)") (class "Default")
      (node (ref "C14") (pin "1") (pinfunction "1_1") (pintype "passive"))
      (node (ref "JP7") (pin "1") (pinfunction "1_1") (pintype "passive"))
      (node (ref "U3") (pin "1") (pinfunction "VDD_1") (pintype "power_in"))
    )
    (net (code "30") (name "Net-(U5-B1)") (class "Default")
      (node (ref "R7") (pin "1") (pinfunction "1_1") (pintype "passive"))
      (node (ref "U5") (pin "3") (pinfunction "B1_3") (pintype "bidirectional"))
    )
    (net (code "31") (name "Net-(U9-VBAT)") (class "Default")
      (node (ref "BT1") (pin "POWER0") (pinfunction "+_POWER0") (pintype "bidirectional"))
      (node (ref "BT1") (pin "POWER1") (pinfunction "+_POWER1") (pintype "bidirectional"))
      (node (ref "C13") (pin "1") (pinfunction "1_1") (pintype "passive"))
      (node (ref "U9") (pin "3") (pinfunction "VBAT_3") (pintype "bidirectional"))
    )
    (net (code "32") (name "Net-(U9-X1)") (class "Default")
      (node (ref "C1") (pin "1") (pinfunction "1_1") (pintype "passive"))
      (node (ref "U9") (pin "1") (pinfunction "X1_1") (pintype "bidirectional"))
      (node (ref "XTAL1") (pin "P$1") (pinfunction "1_P$1") (pintype "passive"))
    )
    (net (code "33") (name "Net-(U9-X2)") (class "Default")
      (node (ref "C2") (pin "1") (pinfunction "1_1") (pintype "passive"))
      (node (ref "U9") (pin "2") (pinfunction "X2_2") (pintype "bidirectional"))
      (node (ref "XTAL1") (pin "P$2") (pinfunction "2_P$2") (pintype "passive"))
    )
    (net (code "34") (name "PAR_INT") (class "Default")
      (node (ref "TP9") (pin "1") (pinfunction "P$1_1") (pintype "bidirectional"))
      (node (ref "U6") (pin "5") (pinfunction "~{INT}_5") (pintype "output"))
      (node (ref "U8") (pin "13") (pinfunction "GP4_13") (pintype "bidirectional"))
    )
    (net (code "35") (name "PWR_P1") (class "Default")
      (node (ref "J1") (pin "3") (pinfunction "3_3") (pintype "passive"))
      (node (ref "JP8") (pin "2") (pinfunction "2_2") (pintype "passive"))
    )
    (net (code "36") (name "RST") (class "Default")
      (node (ref "MS1") (pin "1") (pinfunction "~{RESET}_1") (pintype "input"))
      (node (ref "U3") (pin "6") (pinfunction "RSTN_6") (pintype "output"))
      (node (ref "U8") (pin "4") (pinfunction "~{RESET}_4") (pintype "input"))
    )
    (net (code "37") (name "RTC_INT") (class "Default")
      (node (ref "MS1") (pin "20") (pinfunction "GPIO6_20") (pintype "bidirectional"))
      (node (ref "R9") (pin "1") (pinfunction "1_1") (pintype "passive"))
      (node (ref "TP7") (pin "1") (pinfunction "P$1_1") (pintype "bidirectional"))
      (node (ref "U9") (pin "7") (pinfunction "MFP_7") (pintype "bidirectional"))
    )
    (net (code "38") (name "SCK") (class "Default")
      (node (ref "MS1") (pin "11") (pinfunction "GPIOSCK_11") (pintype "bidirectional"))
      (node (ref "U25") (pin "3") (pinfunction "2A_3") (pintype "input"))
    )
    (net (code "39") (name "SCK_BUF") (class "Default")
      (node (ref "SD1") (pin "5") (pinfunction "SCLK_5") (pintype "bidirectional"))
      (node (ref "U25") (pin "5") (pinfunction "2Y_5") (pintype "output"))
    )
    (net (code "40") (name "SCL") (class "Default")
      (node (ref "MS1") (pin "18") (pinfunction "GPIOSCL_18") (pintype "bidirectional"))
      (node (ref "TP5") (pin "1") (pinfunction "P$1_1") (pintype "bidirectional"))
      (node (ref "U4") (pin "4") (pinfunction "A2_4") (pintype "bidirectional"))
      (node (ref "U6") (pin "2") (pinfunction "SCL_2") (pintype "input"))
      (node (ref "U7") (pin "2") (pinfunction "SCL_2") (pintype "input"))
      (node (ref "U8") (pin "19") (pinfunction "SCL_19") (pintype "input"))
      (node (ref "U9") (pin "6") (pinfunction "SCL_6") (pintype "bidirectional"))
    )
    (net (code "41") (name "SCL_EXT") (class "Default")
      (node (ref "J4") (pin "1") (pinfunction "1_1") (pintype "passive"))
      (node (ref "JP1") (pin "3") (pinfunction "3_3") (pintype "passive"))
      (node (ref "JP3") (pin "3") (pinfunction "3_3") (pintype "passive"))
      (node (ref "JP5") (pin "3") (pinfunction "3_3") (pintype "passive"))
      (node (ref "U4") (pin "1") (pinfunction "B2_1") (pintype "bidirectional"))
    )
    (net (code "42") (name "SDA") (class "Default")
      (node (ref "JP10") (pin "2") (pinfunction "2_2") (pintype "passive"))
      (node (ref "MS1") (pin "17") (pinfunction "GPIOSDA_17") (pintype "bidirectional"))
      (node (ref "TP4") (pin "1") (pinfunction "P$1_1") (pintype "bidirectional"))
      (node (ref "U4") (pin "5") (pinfunction "A1_5") (pintype "bidirectional"))
      (node (ref "U5") (pin "4") (pinfunction "A_4") (pintype "bidirectional"))
    )
    (net (code "43") (name "SDA_CTRL") (class "Default")
      (node (ref "MS1") (pin "19") (pinfunction "GPIO5_19") (pintype "bidirectional"))
      (node (ref "R6") (pin "2") (pinfunction "2_2") (pintype "passive"))
      (node (ref "U5") (pin "6") (pinfunction "S_6") (pintype "input"))
    )
    (net (code "44") (name "SDA_EXT") (class "Default")
      (node (ref "J4") (pin "2") (pinfunction "2_2") (pintype "passive"))
      (node (ref "JP2") (pin "3") (pinfunction "3_3") (pintype "passive"))
      (node (ref "JP4") (pin "3") (pinfunction "3_3") (pintype "passive"))
      (node (ref "JP6") (pin "3") (pinfunction "3_3") (pintype "passive"))
      (node (ref "U4") (pin "8") (pinfunction "B1_8") (pintype "bidirectional"))
    )
    (net (code "45") (name "SDA_OB") (class "Default")
      (node (ref "JP10") (pin "1") (pinfunction "1_1") (pintype "passive"))
      (node (ref "TP6") (pin "1") (pinfunction "P$1_1") (pintype "bidirectional"))
      (node (ref "U5") (pin "1") (pinfunction "B2_1") (pintype "bidirectional"))
      (node (ref "U6") (pin "6") (pinfunction "SDA_6") (pintype "bidirectional"))
      (node (ref "U7") (pin "3") (pinfunction "SDA_3") (pintype "bidirectional"))
      (node (ref "U8") (pin "20") (pinfunction "SDA_20") (pintype "bidirectional"))
      (node (ref "U9") (pin "5") (pinfunction "SDA_5") (pintype "bidirectional"))
    )
    (net (code "46") (name "SD_CD") (class "Default")
      (node (ref "R12") (pin "1") (pinfunction "1_1") (pintype "passive"))
      (node (ref "SD1") (pin "CD1") (pinfunction "CARD_DETECT_CD1") (pintype "bidirectional"))
      (node (ref "U8") (pin "11") (pinfunction "GP2_11") (pintype "bidirectional"))
    )
    (net (code "47") (name "SD_CS") (class "Default")
      (node (ref "MS1") (pin "10") (pinfunction "GPIOA5_10") (pintype "bidirectional"))
      (node (ref "U25") (pin "6") (pinfunction "3A_6") (pintype "input"))
    )
    (net (code "48") (name "SD_CS_BUF") (class "Default")
      (node (ref "SD1") (pin "2") (pinfunction "CS_2") (pintype "bidirectional"))
      (node (ref "U25") (pin "2") (pinfunction "3Y_2") (pintype "output"))
    )
    (net (code "49") (name "TIP") (class "Default")
      (node (ref "J6") (pin "P1") (pinfunction "1_P1") (pintype "passive"))
      (node (ref "MS1") (pin "9") (pinfunction "GPIOA4_9") (pintype "bidirectional"))
      (node (ref "R8") (pin "2") (pinfunction "2_2") (pintype "passive"))
      (node (ref "TP8") (pin "1") (pinfunction "P$1_1") (pintype "bidirectional"))
    )
    (net (code "50") (name "VBAT-") (class "Default")
      (node (ref "J7") (pin "2") (pinfunction "2_2") (pintype "passive"))
      (node (ref "Q1") (pin "3") (pinfunction "D_3") (pintype "bidirectional"))
    )
    (net (code "51") (name "VBAT_FEATHER") (class "Default")
      (node (ref "J7") (pin "1") (pinfunction "1_1") (pintype "passive"))
      (node (ref "MS1") (pin "28") (pinfunction "VBAT_28") (pintype "power_in"))
      (node (ref "Q1") (pin "1") (pinfunction "G_1") (pintype "bidirectional"))
    )
    (net (code "52") (name "VBUS_FEATHER") (class "Default")
      (node (ref "J8") (pin "1") (pinfunction "1_1") (pintype "passive"))
      (node (ref "MS1") (pin "26") (pinfunction "USB_26") (pintype "power_in"))
      (node (ref "Q2") (pin "1") (pinfunction "G_1") (pintype "bidirectional"))
    )
    (net (code "53") (name "VSYS-") (class "Default")
      (node (ref "J8") (pin "2") (pinfunction "2_2") (pintype "passive"))
      (node (ref "Q2") (pin "3") (pinfunction "D_3") (pintype "bidirectional"))
    )
    (net (code "54") (name "WAKE") (class "Default")
      (node (ref "U3") (pin "5") (pinfunction "WAKE_5") (pintype "output"))
      (node (ref "U8") (pin "14") (pinfunction "GP5_14") (pintype "bidirectional"))
    )
    (net (code "55") (name "WD_HOLD") (class "Default")
      (node (ref "MS1") (pin "24") (pinfunction "GPIO12_24") (pintype "bidirectional"))
      (node (ref "U3") (pin "4") (pinfunction "DONE_4") (pintype "input"))
    )
    (net (code "56") (name "unconnected-(MS1-AREF-Pad3)") (class "Default")
      (node (ref "MS1") (pin "3") (pinfunction "AREF_3") (pintype "passive"))
    )
    (net (code "57") (name "unconnected-(MS1-EN-Pad27)") (class "Default")
      (node (ref "MS1") (pin "27") (pinfunction "EN_27") (pintype "passive"))
    )
    (net (code "58") (name "unconnected-(MS1-NC-Pad16)") (class "Default")
      (node (ref "MS1") (pin "16") (pinfunction "NC_16") (pintype "passive"))
    )
    (net (code "59") (name "unconnected-(SD1-DAT1-Pad8)") (class "Default")
      (node (ref "SD1") (pin "8") (pinfunction "DAT1_8") (pintype "bidirectional"))
    )
    (net (code "60") (name "unconnected-(SD1-DAT2-Pad1)") (class "Default")
      (node (ref "SD1") (pin "1") (pinfunction "DAT2_1") (pintype "bidirectional"))
    )
    (net (code "61") (name "unconnected-(U8-GP6-Pad15)") (class "Default")
      (node (ref "U8") (pin "15") (pinfunction "GP6_15") (pintype "bidirectional"))
    )
    (net (code "62") (name "unconnected-(U8-GP7-Pad16)") (class "Default")
      (node (ref "U8") (pin "16") (pinfunction "GP7_16") (pintype "bidirectional"))
    )
  )
)
